# Motor_and_Gyro.net
KiCad netlist of a schematic drawn in Altium Designer
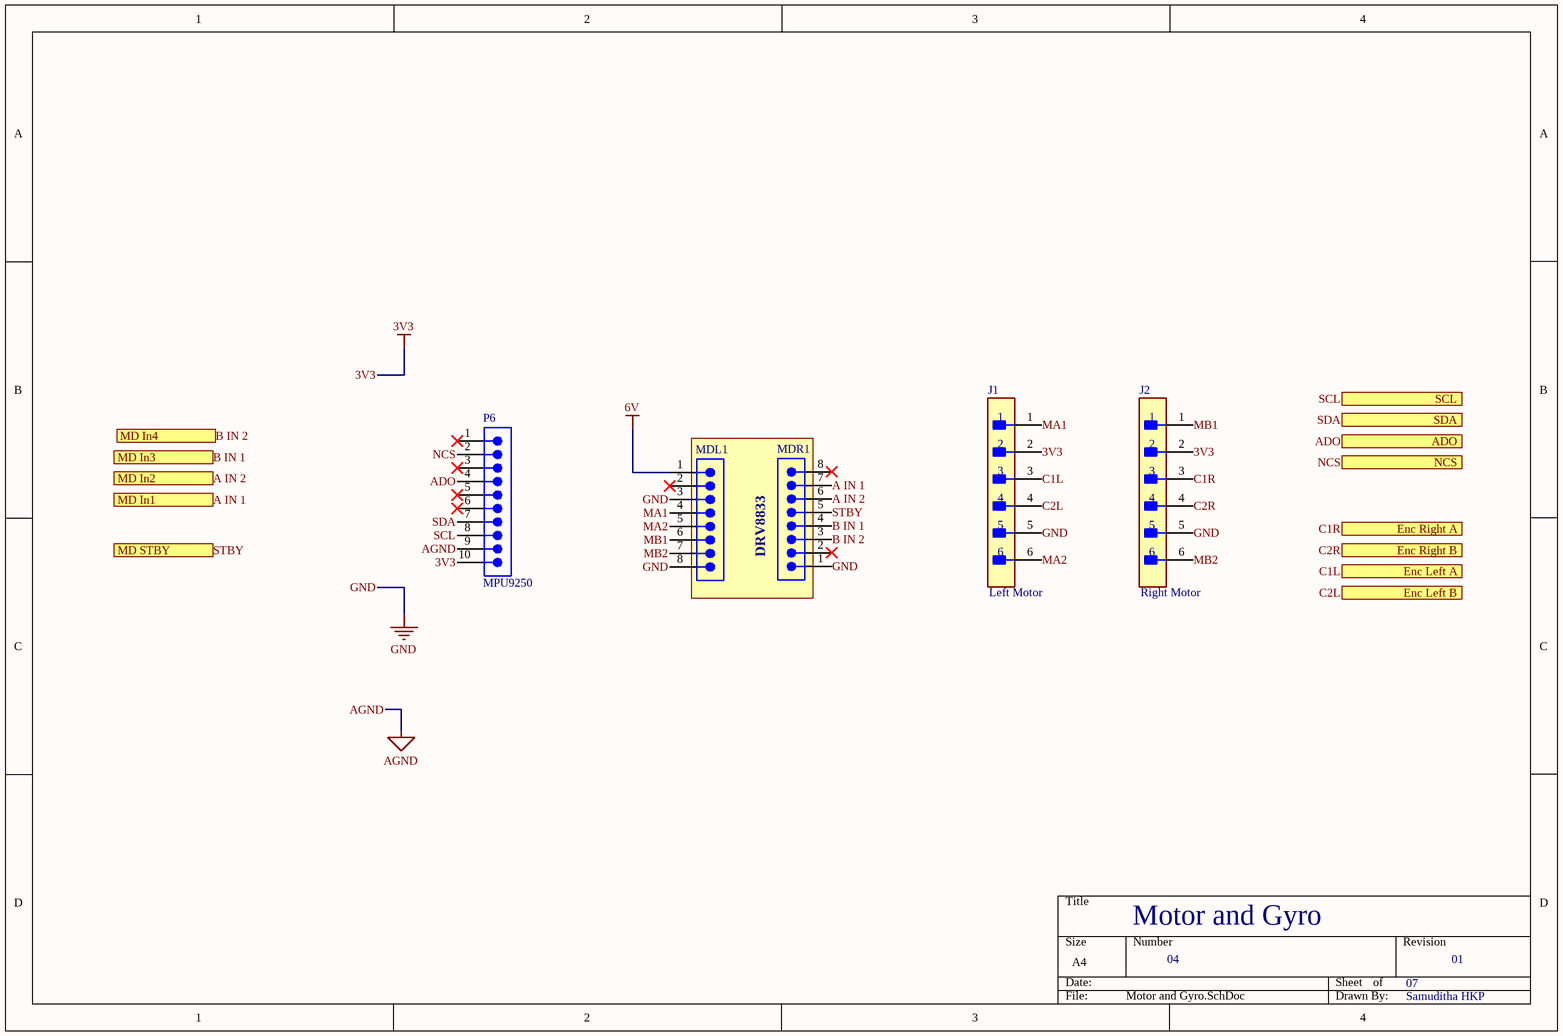
[diagram p0: Motor and Gyro.SchDoc]

(export (version "E")
  (design (tool "Eeschema 10.0.6"))
  (components
    (comp (ref "J1")
      (value "Left Motor")
      (footprint "FP-B6B-EH-A_LF_SN-MFG")
      (description "CONN HEADER VERT 6POS 2.5MM")
      (libsource (lib "Altium Content Vault") (part "f2cb566baf1c37ab5a3b8e90bbeafd6"))
    )
    (comp (ref "J2")
      (value "Right Motor")
      (footprint "FP-B6B-EH-A_LF_SN-MFG")
      (description "CONN HEADER VERT 6POS 2.5MM")
      (libsource (lib "Altium Content Vault") (part "f2cb566baf1c37ab5a3b8e90bbeafd6"))
    )
    (comp (ref "MDL1")
      (value "61300811121")
      (footprint "61300811121")
      (libsource (lib "Altium Content Vault") (part "Header_Male_1R_08P"))
    )
    (comp (ref "MDR1")
      (value "61300811121")
      (footprint "61300811121")
      (libsource (lib "Altium Content Vault") (part "Header_Male_1R_08P"))
    )
    (comp (ref "P6")
      (value "MPU9250")
      (footprint "61301011121")
      (libsource (lib "Altium Content Vault") (part "Header_Male_1R_10P"))
    )
  )
  (nets
    (net (code "1") (name "/A IN 1") (class "Default")
      (node (ref "MDR1") (pin "7") (pinfunction "7_7") (pintype "passive"))
    )
    (net (code "2") (name "/A IN 2") (class "Default")
      (node (ref "MDR1") (pin "6") (pinfunction "6_6") (pintype "passive"))
    )
    (net (code "3") (name "/ADO") (class "Default")
      (node (ref "P6") (pin "4") (pinfunction "4_4") (pintype "passive"))
    )
    (net (code "4") (name "/B IN 1") (class "Default")
      (node (ref "MDR1") (pin "4") (pinfunction "4_4") (pintype "passive"))
    )
    (net (code "5") (name "/B IN 2") (class "Default")
      (node (ref "MDR1") (pin "3") (pinfunction "3_3") (pintype "passive"))
    )
    (net (code "6") (name "/C1L") (class "Default")
      (node (ref "J1") (pin "3") (pinfunction "3_3") (pintype "passive"))
    )
    (net (code "7") (name "/C1R") (class "Default")
      (node (ref "J2") (pin "3") (pinfunction "3_3") (pintype "passive"))
    )
    (net (code "8") (name "/C2L") (class "Default")
      (node (ref "J1") (pin "4") (pinfunction "4_4") (pintype "passive"))
    )
    (net (code "9") (name "/C2R") (class "Default")
      (node (ref "J2") (pin "4") (pinfunction "4_4") (pintype "passive"))
    )
    (net (code "14") (name "/MA1") (class "Default")
      (node (ref "J1") (pin "1") (pinfunction "1_1") (pintype "passive"))
      (node (ref "MDL1") (pin "4") (pinfunction "4_4") (pintype "passive"))
    )
    (net (code "15") (name "/MA2") (class "Default")
      (node (ref "J1") (pin "6") (pinfunction "6_6") (pintype "passive"))
      (node (ref "MDL1") (pin "5") (pinfunction "5_5") (pintype "passive"))
    )
    (net (code "16") (name "/MB1") (class "Default")
      (node (ref "J2") (pin "1") (pinfunction "1_1") (pintype "passive"))
      (node (ref "MDL1") (pin "6") (pinfunction "6_6") (pintype "passive"))
    )
    (net (code "17") (name "/MB2") (class "Default")
      (node (ref "J2") (pin "6") (pinfunction "6_6") (pintype "passive"))
      (node (ref "MDL1") (pin "7") (pinfunction "7_7") (pintype "passive"))
    )
    (net (code "18") (name "/NCS") (class "Default")
      (node (ref "P6") (pin "2") (pinfunction "2_2") (pintype "passive"))
    )
    (net (code "19") (name "/SCL") (class "Default")
      (node (ref "P6") (pin "8") (pinfunction "8_8") (pintype "passive"))
    )
    (net (code "20") (name "/SDA") (class "Default")
      (node (ref "P6") (pin "7") (pinfunction "7_7") (pintype "passive"))
    )
    (net (code "21") (name "/STBY") (class "Default")
      (node (ref "MDR1") (pin "5") (pinfunction "5_5") (pintype "passive"))
    )
    (net (code "22") (name "3V3") (class "Default")
      (node (ref "J1") (pin "2") (pinfunction "2_2") (pintype "passive"))
      (node (ref "J2") (pin "2") (pinfunction "2_2") (pintype "passive"))
      (node (ref "P6") (pin "10") (pinfunction "10_10") (pintype "passive"))
    )
    (net (code "23") (name "6V") (class "Default")
      (node (ref "MDL1") (pin "1") (pinfunction "1_1") (pintype "passive"))
    )
    (net (code "24") (name "AGND") (class "Default")
      (node (ref "P6") (pin "9") (pinfunction "9_9") (pintype "passive"))
    )
    (net (code "25") (name "GND") (class "Default")
      (node (ref "J1") (pin "5") (pinfunction "5_5") (pintype "passive"))
      (node (ref "J2") (pin "5") (pinfunction "5_5") (pintype "passive"))
      (node (ref "MDL1") (pin "3") (pinfunction "3_3") (pintype "passive"))
      (node (ref "MDL1") (pin "8") (pinfunction "8_8") (pintype "passive"))
      (node (ref "MDR1") (pin "1") (pinfunction "1_1") (pintype "passive"))
    )
    (net (code "26") (name "unconnected-(MDL1-Pad2)") (class "Default")
      (node (ref "MDL1") (pin "2") (pinfunction "2_2") (pintype "passive+no_connect"))
    )
    (net (code "27") (name "unconnected-(MDR1-Pad2)") (class "Default")
      (node (ref "MDR1") (pin "2") (pinfunction "2_2") (pintype "passive+no_connect"))
    )
    (net (code "28") (name "unconnected-(MDR1-Pad8)") (class "Default")
      (node (ref "MDR1") (pin "8") (pinfunction "8_8") (pintype "passive+no_connect"))
    )
    (net (code "29") (name "unconnected-(P6-Pad1)") (class "Default")
      (node (ref "P6") (pin "1") (pinfunction "1_1") (pintype "passive+no_connect"))
    )
    (net (code "30") (name "unconnected-(P6-Pad3)") (class "Default")
      (node (ref "P6") (pin "3") (pinfunction "3_3") (pintype "passive+no_connect"))
    )
    (net (code "31") (name "unconnected-(P6-Pad5)") (class "Default")
      (node (ref "P6") (pin "5") (pinfunction "5_5") (pintype "passive+no_connect"))
    )
    (net (code "32") (name "unconnected-(P6-Pad6)") (class "Default")
      (node (ref "P6") (pin "6") (pinfunction "6_6") (pintype "passive+no_connect"))
    )
  )
)
